# Base.net
KiCad netlist of a schematic drawn in EAGLE
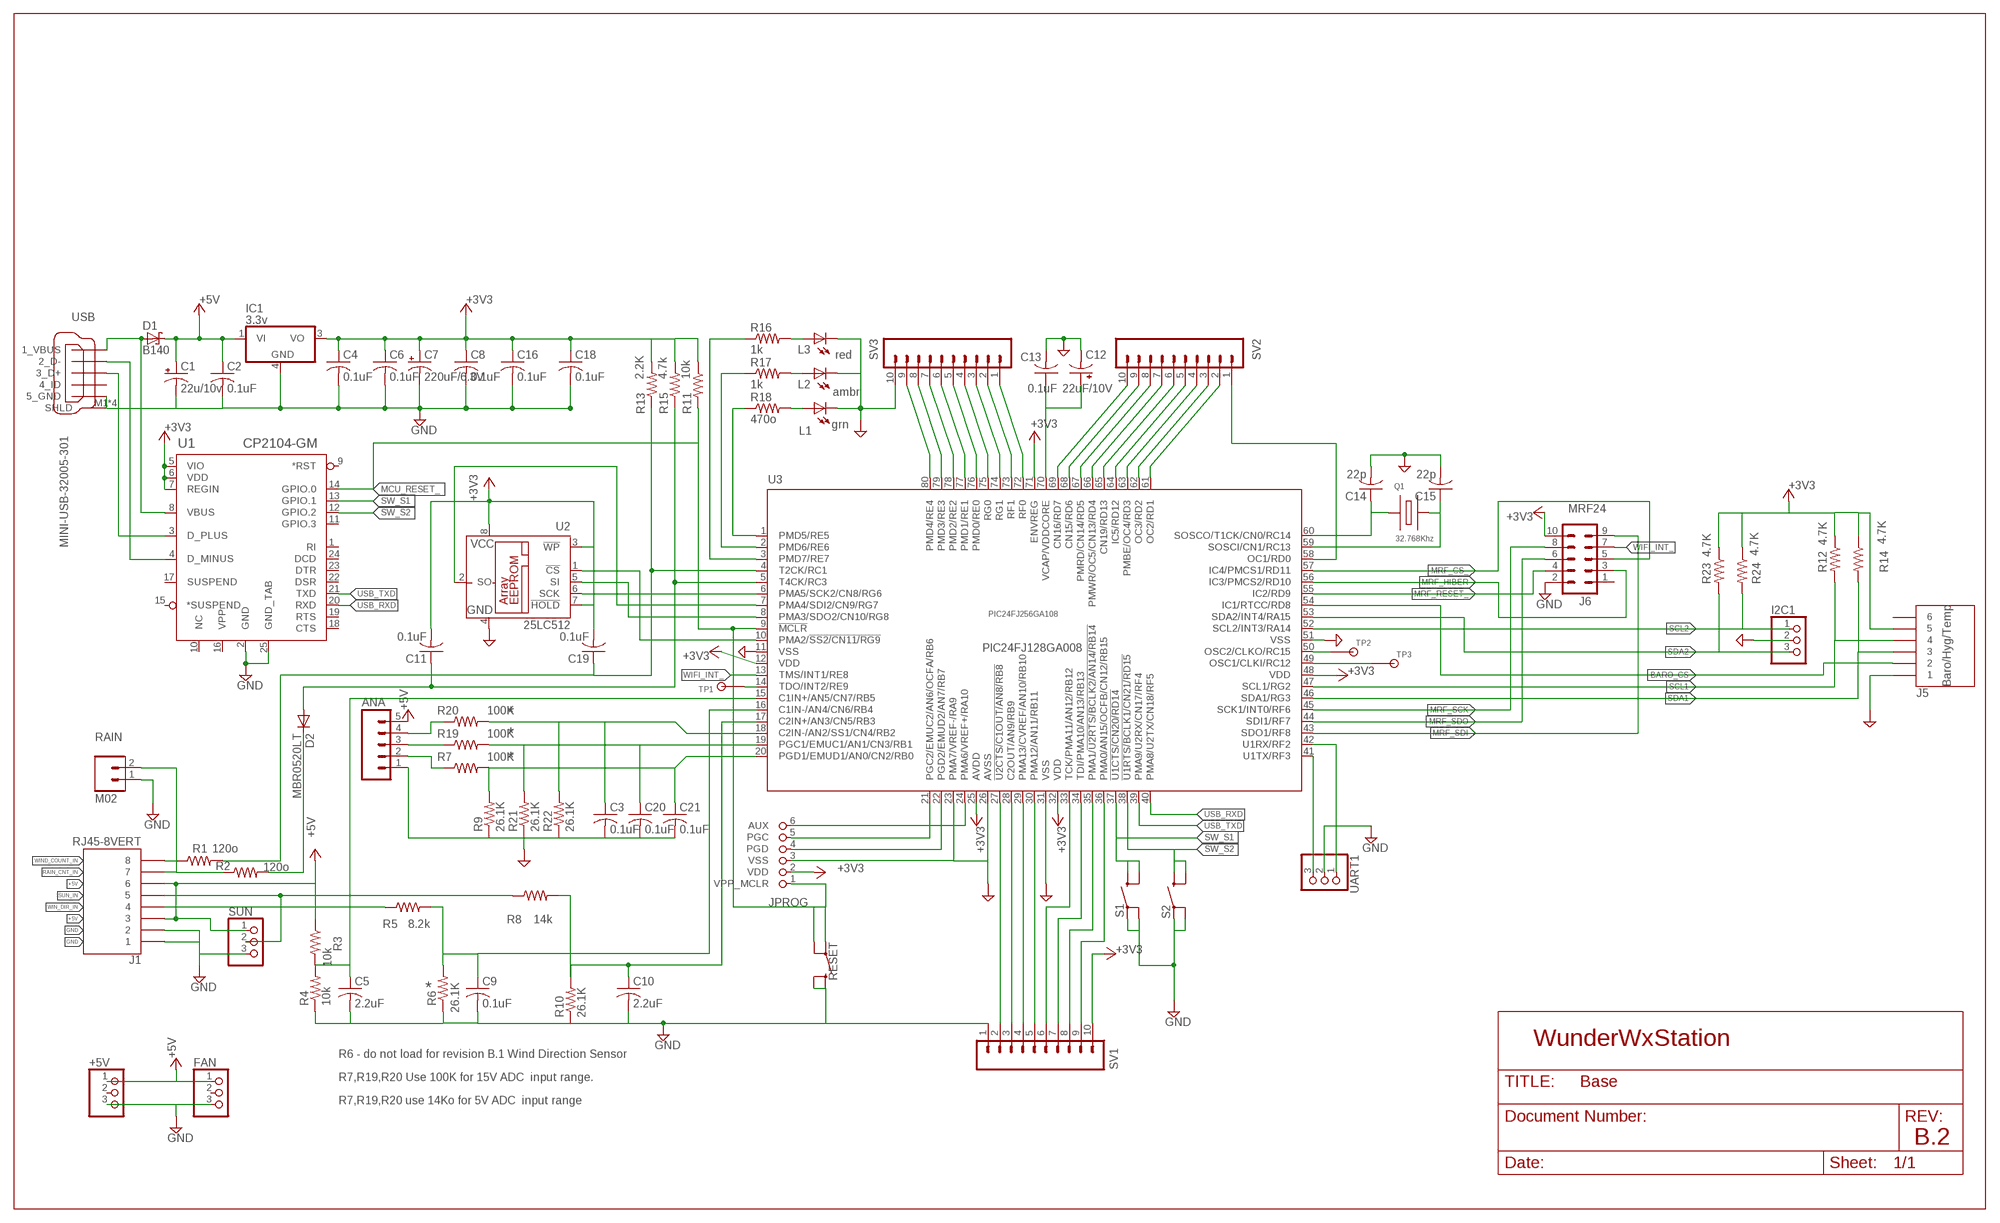
[diagram p0: schematic, sheet 1]

(export (version "E")
  (design (tool "Eeschema 10.0.6"))
  (components
    (comp (ref "+5V")
      (value "PINHD-1X3MOLEX_KK")
      (footprint "eagle-import:1X3_MOLEX_KK")
      (libsource (lib "eagle-import") (part "PINHD-1X3MOLEX_KK"))
    )
    (comp (ref "ANA")
      (value "M05PTH")
      (footprint "eagle-import:1X05")
      (libsource (lib "eagle-import") (part "M05PTH"))
    )
    (comp (ref "C1")
      (value "22u/10v")
      (footprint "eagle-import:SMC_B")
      (libsource (lib "eagle-import") (part "CPOL-USSMCB"))
    )
    (comp (ref "C2")
      (value "0.1uF")
      (footprint "eagle-import:C0805")
      (libsource (lib "eagle-import") (part "C-USC0805"))
    )
    (comp (ref "C3")
      (value "0.1uF")
      (footprint "eagle-import:C0805")
      (libsource (lib "eagle-import") (part "C-USC0805"))
    )
    (comp (ref "C4")
      (value "0.1uF")
      (footprint "eagle-import:C0805")
      (libsource (lib "eagle-import") (part "C-USC0805"))
    )
    (comp (ref "C5")
      (value "2.2uF")
      (footprint "eagle-import:C0805")
      (libsource (lib "eagle-import") (part "C-USC0805"))
    )
    (comp (ref "C6")
      (value "0.1uF")
      (footprint "eagle-import:C0805")
      (libsource (lib "eagle-import") (part "C-USC0805"))
    )
    (comp (ref "C7")
      (value "220uF/6.3V")
      (footprint "eagle-import:SMC_D")
      (libsource (lib "eagle-import") (part "CPOL-USSMCD"))
    )
    (comp (ref "C8")
      (value "0.1uF")
      (footprint "eagle-import:C0805")
      (libsource (lib "eagle-import") (part "C-USC0805"))
    )
    (comp (ref "C9")
      (value "0.1uF")
      (footprint "eagle-import:C0805")
      (libsource (lib "eagle-import") (part "C-USC0805"))
    )
    (comp (ref "C10")
      (value "2.2uF")
      (footprint "eagle-import:C0805")
      (libsource (lib "eagle-import") (part "C-USC0805"))
    )
    (comp (ref "C11")
      (value "0.1uF")
      (footprint "eagle-import:C0805")
      (libsource (lib "eagle-import") (part "C-USC0805"))
    )
    (comp (ref "C12")
      (value "22uF/10V")
      (footprint "eagle-import:SMC_B")
      (libsource (lib "eagle-import") (part "CPOL-USSMCB"))
    )
    (comp (ref "C13")
      (value "0.1uF")
      (footprint "eagle-import:C0805")
      (libsource (lib "eagle-import") (part "C-USC0805"))
    )
    (comp (ref "C14")
      (value "22p")
      (footprint "eagle-import:C0603")
      (libsource (lib "eagle-import") (part "C-USC0603"))
    )
    (comp (ref "C15")
      (value "22p")
      (footprint "eagle-import:C0603")
      (libsource (lib "eagle-import") (part "C-USC0603"))
    )
    (comp (ref "C16")
      (value "0.1uF")
      (footprint "eagle-import:C0805")
      (libsource (lib "eagle-import") (part "C-USC0805"))
    )
    (comp (ref "C18")
      (value "0.1uF")
      (footprint "eagle-import:C0805")
      (libsource (lib "eagle-import") (part "C-USC0805"))
    )
    (comp (ref "C19")
      (value "0.1uF")
      (footprint "eagle-import:C0805")
      (libsource (lib "eagle-import") (part "C-USC0805"))
    )
    (comp (ref "C20")
      (value "0.1uF")
      (footprint "eagle-import:C0805")
      (libsource (lib "eagle-import") (part "C-USC0805"))
    )
    (comp (ref "C21")
      (value "0.1uF")
      (footprint "eagle-import:C0805")
      (libsource (lib "eagle-import") (part "C-USC0805"))
    )
    (comp (ref "D1")
      (value "B140")
      (footprint "eagle-import:SMB")
      (libsource (lib "eagle-import") (part "SCHOTTKY-DIODESMD"))
    )
    (comp (ref "D2")
      (value "MBR0520LT")
      (footprint "eagle-import:SOD123")
      (libsource (lib "eagle-import") (part "MBR0520LT"))
    )
    (comp (ref "FAN")
      (value "PINHD-1X3MOLEX_KK")
      (footprint "eagle-import:1X3_MOLEX_KK")
      (libsource (lib "eagle-import") (part "PINHD-1X3MOLEX_KK"))
    )
    (comp (ref "I2C1")
      (value "PINHD-1X3")
      (footprint "eagle-import:1X03")
      (libsource (lib "eagle-import") (part "PINHD-1X3"))
    )
    (comp (ref "IC1")
      (value "3.3v")
      (footprint "eagle-import:DPACK")
      (libsource (lib "eagle-import") (part "78MXXL"))
    )
    (comp (ref "J1")
      (value "RJ45-8VERT")
      (footprint "eagle-import:RJ45_VERT")
      (libsource (lib "eagle-import") (part "RJ45-8VERT"))
    )
    (comp (ref "J5")
      (value "RJ11-6VERT_LP")
      (footprint "eagle-import:RJ11-6-VERT")
      (libsource (lib "eagle-import") (part "RJ11-6VERT_LP"))
    )
    (comp (ref "J6")
      (value "M05X22X5FE")
      (footprint "eagle-import:2X5FEMALE")
      (libsource (lib "eagle-import") (part "M05X22X5FE"))
    )
    (comp (ref "JPROG")
      (value "PIKIT2_PRG")
      (footprint "eagle-import:1X06_PIKIT")
      (libsource (lib "eagle-import") (part "PIKIT2_PRG"))
    )
    (comp (ref "L1")
      (value "grn")
      (footprint "eagle-import:CHIP-LED0603")
      (libsource (lib "eagle-import") (part "LEDCHIP-LED0603"))
    )
    (comp (ref "L2")
      (value "ambr")
      (footprint "eagle-import:CHIP-LED0603")
      (libsource (lib "eagle-import") (part "LEDCHIP-LED0603"))
    )
    (comp (ref "L3")
      (value "red")
      (footprint "eagle-import:CHIP-LED0603")
      (libsource (lib "eagle-import") (part "LEDCHIP-LED0603"))
    )
    (comp (ref "Q1")
      (value "32.768Khz")
      (footprint "eagle-import:CRYSTAL32_SMT")
      (libsource (lib "eagle-import") (part "CRYSTAL"))
    )
    (comp (ref "R1")
      (value "120o")
      (footprint "eagle-import:R0603")
      (libsource (lib "eagle-import") (part "R-US_R0603"))
    )
    (comp (ref "R2")
      (value "120o")
      (footprint "eagle-import:R0603")
      (libsource (lib "eagle-import") (part "R-US_R0603"))
    )
    (comp (ref "R3")
      (value "10k")
      (footprint "eagle-import:R0603")
      (libsource (lib "eagle-import") (part "R-US_R0603"))
    )
    (comp (ref "R4")
      (value "10k")
      (footprint "eagle-import:R0603")
      (libsource (lib "eagle-import") (part "R-US_R0603"))
    )
    (comp (ref "R5")
      (value "8.2k")
      (footprint "eagle-import:R0603")
      (libsource (lib "eagle-import") (part "R-US_R0603"))
    )
    (comp (ref "R6")
      (value "26.1K")
      (footprint "eagle-import:R0603")
      (libsource (lib "eagle-import") (part "R-US_R0603"))
    )
    (comp (ref "R7")
      (value "100K")
      (footprint "eagle-import:R0603")
      (libsource (lib "eagle-import") (part "R-US_R0603"))
    )
    (comp (ref "R8")
      (value "14k")
      (footprint "eagle-import:R0603")
      (libsource (lib "eagle-import") (part "R-US_R0603"))
    )
    (comp (ref "R9")
      (value "26.1K")
      (footprint "eagle-import:R0603")
      (libsource (lib "eagle-import") (part "R-US_R0603"))
    )
    (comp (ref "R10")
      (value "26.1K")
      (footprint "eagle-import:R0603")
      (libsource (lib "eagle-import") (part "R-US_R0603"))
    )
    (comp (ref "R11")
      (value "10k")
      (footprint "eagle-import:R0603")
      (libsource (lib "eagle-import") (part "R-US_R0603"))
    )
    (comp (ref "R12")
      (value "4.7K")
      (footprint "eagle-import:R0603")
      (libsource (lib "eagle-import") (part "R-US_R0603"))
    )
    (comp (ref "R13")
      (value "2.2K")
      (footprint "eagle-import:R0603")
      (libsource (lib "eagle-import") (part "R-US_R0603"))
    )
    (comp (ref "R14")
      (value "4.7K")
      (footprint "eagle-import:R0603")
      (libsource (lib "eagle-import") (part "R-US_R0603"))
    )
    (comp (ref "R15")
      (value "4.7k")
      (footprint "eagle-import:R0603")
      (libsource (lib "eagle-import") (part "R-US_R0603"))
    )
    (comp (ref "R16")
      (value "1k")
      (footprint "eagle-import:R0603")
      (libsource (lib "eagle-import") (part "R-US_R0603"))
    )
    (comp (ref "R17")
      (value "1k")
      (footprint "eagle-import:R0603")
      (libsource (lib "eagle-import") (part "R-US_R0603"))
    )
    (comp (ref "R18")
      (value "470o")
      (footprint "eagle-import:R0603")
      (libsource (lib "eagle-import") (part "R-US_R0603"))
    )
    (comp (ref "R19")
      (value "100K")
      (footprint "eagle-import:R0603")
      (libsource (lib "eagle-import") (part "R-US_R0603"))
    )
    (comp (ref "R20")
      (value "100K")
      (footprint "eagle-import:R0603")
      (libsource (lib "eagle-import") (part "R-US_R0603"))
    )
    (comp (ref "R21")
      (value "26.1K")
      (footprint "eagle-import:R0603")
      (libsource (lib "eagle-import") (part "R-US_R0603"))
    )
    (comp (ref "R22")
      (value "26.1K")
      (footprint "eagle-import:R0603")
      (libsource (lib "eagle-import") (part "R-US_R0603"))
    )
    (comp (ref "R23")
      (value "4.7K")
      (footprint "eagle-import:R0603")
      (libsource (lib "eagle-import") (part "R-US_R0603"))
    )
    (comp (ref "R24")
      (value "4.7K")
      (footprint "eagle-import:R0603")
      (libsource (lib "eagle-import") (part "R-US_R0603"))
    )
    (comp (ref "RAIN")
      (value "M02")
      (footprint "eagle-import:1X02")
      (libsource (lib "eagle-import") (part "M02"))
    )
    (comp (ref "RESET")
      (value "SWITCH-MOMENTARY-2SMD")
      (footprint "eagle-import:TACTILE_SWITCH_SMD")
      (libsource (lib "eagle-import") (part "SWITCH-MOMENTARY-2SMD"))
    )
    (comp (ref "S1")
      (value "SWITCH-MOMENTARY-2SMD")
      (footprint "eagle-import:TACTILE_SWITCH_SMD")
      (libsource (lib "eagle-import") (part "SWITCH-MOMENTARY-2SMD"))
    )
    (comp (ref "S2")
      (value "SWITCH-MOMENTARY-2SMD")
      (footprint "eagle-import:TACTILE_SWITCH_SMD")
      (libsource (lib "eagle-import") (part "SWITCH-MOMENTARY-2SMD"))
    )
    (comp (ref "SUN")
      (value "PINHD-1X3MOLEX_KK")
      (footprint "eagle-import:1X3_MOLEX_KK")
      (libsource (lib "eagle-import") (part "PINHD-1X3MOLEX_KK"))
    )
    (comp (ref "SV1")
      (value "M10\"")
      (footprint "eagle-import:1X10")
      (libsource (lib "eagle-import") (part "M10{dblquote}"))
    )
    (comp (ref "SV2")
      (value "M10\"")
      (footprint "eagle-import:1X10")
      (libsource (lib "eagle-import") (part "M10{dblquote}"))
    )
    (comp (ref "SV3")
      (value "M10\"")
      (footprint "eagle-import:1X10")
      (libsource (lib "eagle-import") (part "M10{dblquote}"))
    )
    (comp (ref "TP1")
      (value "TP10R")
      (footprint "eagle-import:TP10R")
      (libsource (lib "eagle-import") (part "TP10R"))
    )
    (comp (ref "TP2")
      (value "TP6R")
      (footprint "eagle-import:TP06R")
      (libsource (lib "eagle-import") (part "TP6R"))
    )
    (comp (ref "TP3")
      (value "TP6R")
      (footprint "eagle-import:TP06R")
      (libsource (lib "eagle-import") (part "TP6R"))
    )
    (comp (ref "U1")
      (value "CP2104-GM")
      (footprint "eagle-import:QFN24_4X4")
      (libsource (lib "eagle-import") (part "CP2104-GM"))
    )
    (comp (ref "U2")
      (value "25LC512")
      (footprint "eagle-import:SO-08")
      (fields (field (name "MF") "MICROCHIP") (field (name "MPN") "25LC080/SN"))
      (libsource (lib "eagle-import") (part "25SNLC080"))
    )
    (comp (ref "U3")
      (value "PIC24FJ128GA008")
      (footprint "eagle-import:TQFP80-12X12")
      (fields (field (name "MF") "MICROCHIP") (field (name "MPN") "PIC24FJ128GA008-I/PT"))
      (libsource (lib "eagle-import") (part "PIC24FJGA008128"))
    )
    (comp (ref "UART1")
      (value "PINHD-1X3")
      (footprint "eagle-import:1X03")
      (libsource (lib "eagle-import") (part "PINHD-1X3"))
    )
    (comp (ref "USB")
      (value "MINI-USB-32005-301")
      (footprint "eagle-import:32005-301")
      (libsource (lib "eagle-import") (part "MINI-USB-32005-301"))
    )
  )
  (nets
    (net (code "1") (name "+3V3") (class "Default")
      (node (ref "C11") (pin "2") (pinfunction "2_2") (pintype "passive"))
      (node (ref "C16") (pin "1") (pinfunction "1_1") (pintype "passive"))
      (node (ref "C18") (pin "1") (pinfunction "1_1") (pintype "passive"))
      (node (ref "C19") (pin "2") (pinfunction "2_2") (pintype "passive"))
      (node (ref "C4") (pin "1") (pinfunction "1_1") (pintype "passive"))
      (node (ref "C6") (pin "1") (pinfunction "1_1") (pintype "passive"))
      (node (ref "C7") (pin "+") (pinfunction "+_+") (pintype "passive"))
      (node (ref "C8") (pin "1") (pinfunction "1_1") (pintype "passive"))
      (node (ref "IC1") (pin "3") (pinfunction "VO_3") (pintype "passive"))
      (node (ref "J5") (pin "P$5") (pinfunction "5_P$5") (pintype "bidirectional"))
      (node (ref "J6") (pin "10") (pinfunction "10_10") (pintype "passive"))
      (node (ref "JPROG") (pin "2") (pinfunction "VDD_2") (pintype "passive"))
      (node (ref "R11") (pin "1") (pinfunction "1_1") (pintype "passive"))
      (node (ref "R12") (pin "1") (pinfunction "1_1") (pintype "passive"))
      (node (ref "R13") (pin "2") (pinfunction "2_2") (pintype "passive"))
      (node (ref "R14") (pin "1") (pinfunction "1_1") (pintype "passive"))
      (node (ref "R15") (pin "2") (pinfunction "2_2") (pintype "passive"))
      (node (ref "R23") (pin "1") (pinfunction "1_1") (pintype "passive"))
      (node (ref "R24") (pin "1") (pinfunction "1_1") (pintype "passive"))
      (node (ref "SV1") (pin "10") (pinfunction "10_10") (pintype "passive"))
      (node (ref "U1") (pin "5") (pinfunction "VIO_5") (pintype "power_in"))
      (node (ref "U1") (pin "6") (pinfunction "VDD_6") (pintype "power_in"))
      (node (ref "U1") (pin "7") (pinfunction "REGIN_7") (pintype "input"))
      (node (ref "U2") (pin "3") (pinfunction "~{WP}_3") (pintype "input"))
      (node (ref "U2") (pin "7") (pinfunction "~{HOLD}_7") (pintype "input"))
      (node (ref "U2") (pin "8") (pinfunction "VCC_8") (pintype "power_in"))
      (node (ref "U3") (pin "12") (pinfunction "VDD_12") (pintype "power_in"))
      (node (ref "U3") (pin "25") (pinfunction "AVDD_25") (pintype "power_in"))
      (node (ref "U3") (pin "32") (pinfunction "VDD_32") (pintype "power_in"))
      (node (ref "U3") (pin "48") (pinfunction "VDD_48") (pintype "power_in"))
      (node (ref "U3") (pin "71") (pinfunction "ENVREG_71") (pintype "bidirectional"))
    )
    (net (code "2") (name "+5V") (class "Default")
      (node (ref "+5V") (pin "1") (pinfunction "1_1") (pintype "passive"))
      (node (ref "ANA") (pin "5") (pinfunction "5_5") (pintype "passive"))
      (node (ref "C1") (pin "+") (pinfunction "+_+") (pintype "passive"))
      (node (ref "C2") (pin "1") (pinfunction "1_1") (pintype "passive"))
      (node (ref "D1") (pin "C") (pinfunction "C_C") (pintype "passive"))
      (node (ref "FAN") (pin "1") (pinfunction "1_1") (pintype "passive"))
      (node (ref "IC1") (pin "1") (pinfunction "VI_1") (pintype "input"))
      (node (ref "J1") (pin "P$3") (pinfunction "3_P$3") (pintype "bidirectional"))
      (node (ref "J1") (pin "P$6") (pinfunction "6_P$6") (pintype "bidirectional"))
      (node (ref "R3") (pin "1") (pinfunction "1_1") (pintype "passive"))
      (node (ref "SUN") (pin "1") (pinfunction "1_1") (pintype "passive"))
    )
    (net (code "3") (name "BARO_CS") (class "Default")
      (node (ref "J5") (pin "P$2") (pinfunction "2_P$2") (pintype "bidirectional"))
      (node (ref "U3") (pin "54") (pinfunction "IC1/RTCC/RD8_54") (pintype "bidirectional"))
    )
    (net (code "4") (name "GND") (class "Default")
      (node (ref "+5V") (pin "3") (pinfunction "3_3") (pintype "passive"))
      (node (ref "ANA") (pin "1") (pinfunction "1_1") (pintype "passive"))
      (node (ref "C1") (pin "-") (pinfunction "-_-") (pintype "passive"))
      (node (ref "C10") (pin "2") (pinfunction "2_2") (pintype "passive"))
      (node (ref "C12") (pin "-") (pinfunction "-_-") (pintype "passive"))
      (node (ref "C13") (pin "2") (pinfunction "2_2") (pintype "passive"))
      (node (ref "C14") (pin "2") (pinfunction "2_2") (pintype "passive"))
      (node (ref "C15") (pin "2") (pinfunction "2_2") (pintype "passive"))
      (node (ref "C16") (pin "2") (pinfunction "2_2") (pintype "passive"))
      (node (ref "C18") (pin "2") (pinfunction "2_2") (pintype "passive"))
      (node (ref "C2") (pin "2") (pinfunction "2_2") (pintype "passive"))
      (node (ref "C20") (pin "2") (pinfunction "2_2") (pintype "passive"))
      (node (ref "C21") (pin "2") (pinfunction "2_2") (pintype "passive"))
      (node (ref "C3") (pin "2") (pinfunction "2_2") (pintype "passive"))
      (node (ref "C4") (pin "2") (pinfunction "2_2") (pintype "passive"))
      (node (ref "C5") (pin "2") (pinfunction "2_2") (pintype "passive"))
      (node (ref "C6") (pin "2") (pinfunction "2_2") (pintype "passive"))
      (node (ref "C7") (pin "-") (pinfunction "-_-") (pintype "passive"))
      (node (ref "C8") (pin "2") (pinfunction "2_2") (pintype "passive"))
      (node (ref "C9") (pin "2") (pinfunction "2_2") (pintype "passive"))
      (node (ref "FAN") (pin "3") (pinfunction "3_3") (pintype "passive"))
      (node (ref "I2C1") (pin "2") (pinfunction "2_2") (pintype "passive"))
      (node (ref "IC1") (pin "4") (pinfunction "GND_4") (pintype "passive"))
      (node (ref "J1") (pin "P$1") (pinfunction "1_P$1") (pintype "bidirectional"))
      (node (ref "J1") (pin "P$2") (pinfunction "2_P$2") (pintype "bidirectional"))
      (node (ref "J5") (pin "P$1") (pinfunction "1_P$1") (pintype "bidirectional"))
      (node (ref "J6") (pin "2") (pinfunction "2_2") (pintype "passive"))
      (node (ref "JPROG") (pin "3") (pinfunction "VSS_3") (pintype "passive"))
      (node (ref "L1") (pin "C") (pinfunction "C_C") (pintype "passive"))
      (node (ref "L2") (pin "C") (pinfunction "C_C") (pintype "passive"))
      (node (ref "L3") (pin "C") (pinfunction "C_C") (pintype "passive"))
      (node (ref "R10") (pin "1") (pinfunction "1_1") (pintype "passive"))
      (node (ref "R21") (pin "1") (pinfunction "1_1") (pintype "passive"))
      (node (ref "R22") (pin "1") (pinfunction "1_1") (pintype "passive"))
      (node (ref "R4") (pin "1") (pinfunction "1_1") (pintype "passive"))
      (node (ref "R6") (pin "1") (pinfunction "1_1") (pintype "passive"))
      (node (ref "R9") (pin "1") (pinfunction "1_1") (pintype "passive"))
      (node (ref "RAIN") (pin "1") (pinfunction "1_1") (pintype "passive"))
      (node (ref "RESET") (pin "3") (pinfunction "2_3") (pintype "passive"))
      (node (ref "RESET") (pin "4") (pinfunction "3_4") (pintype "passive"))
      (node (ref "S1") (pin "1") (pinfunction "1_1") (pintype "passive"))
      (node (ref "S1") (pin "2") (pinfunction "4_2") (pintype "passive"))
      (node (ref "S2") (pin "1") (pinfunction "1_1") (pintype "passive"))
      (node (ref "S2") (pin "2") (pinfunction "4_2") (pintype "passive"))
      (node (ref "SUN") (pin "3") (pinfunction "3_3") (pintype "passive"))
      (node (ref "SV1") (pin "1") (pinfunction "1_1") (pintype "passive"))
      (node (ref "SV3") (pin "10") (pinfunction "10_10") (pintype "passive"))
      (node (ref "U1") (pin "2") (pinfunction "GND_2") (pintype "power_in"))
      (node (ref "U1") (pin "25") (pinfunction "GND_TAB_25") (pintype "passive"))
      (node (ref "U2") (pin "4") (pinfunction "GND_4") (pintype "power_in"))
      (node (ref "U3") (pin "11") (pinfunction "VSS_11") (pintype "power_in"))
      (node (ref "U3") (pin "23") (pinfunction "PMA7/VREF-/RA9_23") (pintype "bidirectional"))
      (node (ref "U3") (pin "26") (pinfunction "AVSS_26") (pintype "power_in"))
      (node (ref "U3") (pin "31") (pinfunction "VSS_31") (pintype "power_in"))
      (node (ref "U3") (pin "51") (pinfunction "VSS_51") (pintype "power_in"))
      (node (ref "UART1") (pin "2") (pinfunction "2_2") (pintype "passive"))
      (node (ref "USB") (pin "5_USB_GND") (pinfunction "5_GND_5_USB_GND") (pintype "passive"))
      (node (ref "USB") (pin "M1") (pinfunction "SHLD_M1") (pintype "passive"))
      (node (ref "USB") (pin "M2") (pinfunction "SHLD_M2") (pintype "passive"))
      (node (ref "USB") (pin "M3") (pinfunction "SHLD_M3") (pintype "passive"))
      (node (ref "USB") (pin "M4") (pinfunction "SHLD_M4") (pintype "passive"))
    )
    (net (code "5") (name "MCU_RESET_") (class "Default")
      (node (ref "JPROG") (pin "1") (pinfunction "VPP_MCLR_1") (pintype "passive"))
      (node (ref "R11") (pin "2") (pinfunction "2_2") (pintype "passive"))
      (node (ref "RESET") (pin "1") (pinfunction "1_1") (pintype "passive"))
      (node (ref "RESET") (pin "2") (pinfunction "4_2") (pintype "passive"))
      (node (ref "U1") (pin "14") (pinfunction "GPIO.0_14") (pintype "passive"))
      (node (ref "U3") (pin "9") (pinfunction "~{MCLR}_9") (pintype "bidirectional"))
    )
    (net (code "6") (name "MRF_CS_") (class "Default")
      (node (ref "J6") (pin "5") (pinfunction "5_5") (pintype "passive"))
      (node (ref "U3") (pin "57") (pinfunction "IC4/PMCS1/RD11_57") (pintype "bidirectional"))
    )
    (net (code "7") (name "MRF_HIBER") (class "Default")
      (node (ref "J6") (pin "3") (pinfunction "3_3") (pintype "passive"))
      (node (ref "U3") (pin "56") (pinfunction "IC3/PMCS2/RD10_56") (pintype "bidirectional"))
    )
    (net (code "8") (name "MRF_RESET_") (class "Default")
      (node (ref "J6") (pin "4") (pinfunction "4_4") (pintype "passive"))
      (node (ref "U3") (pin "55") (pinfunction "IC2/RD9_55") (pintype "bidirectional"))
    )
    (net (code "9") (name "MRF_SCK") (class "Default")
      (node (ref "J6") (pin "8") (pinfunction "8_8") (pintype "passive"))
      (node (ref "U3") (pin "45") (pinfunction "SCK1/INT0/RF6_45") (pintype "bidirectional"))
    )
    (net (code "10") (name "MRF_SDI") (class "Default")
      (node (ref "J6") (pin "9") (pinfunction "9_9") (pintype "passive"))
      (node (ref "U3") (pin "43") (pinfunction "SDO1/RF8_43") (pintype "bidirectional"))
    )
    (net (code "11") (name "MRF_SDO") (class "Default")
      (node (ref "J6") (pin "6") (pinfunction "6_6") (pintype "passive"))
      (node (ref "U3") (pin "44") (pinfunction "SDI1/RF7_44") (pintype "bidirectional"))
    )
    (net (code "12") (name "Net-(ANA-Pad2)") (class "Default")
      (node (ref "ANA") (pin "2") (pinfunction "2_2") (pintype "passive"))
      (node (ref "R7") (pin "1") (pinfunction "1_1") (pintype "passive"))
    )
    (net (code "13") (name "Net-(ANA-Pad3)") (class "Default")
      (node (ref "ANA") (pin "3") (pinfunction "3_3") (pintype "passive"))
      (node (ref "R19") (pin "1") (pinfunction "1_1") (pintype "passive"))
    )
    (net (code "14") (name "Net-(ANA-Pad4)") (class "Default")
      (node (ref "ANA") (pin "4") (pinfunction "4_4") (pintype "passive"))
      (node (ref "R20") (pin "1") (pinfunction "1_1") (pintype "passive"))
    )
    (net (code "15") (name "Net-(D2-PadC)") (class "Default")
      (node (ref "D2") (pin "C") (pinfunction "C_C") (pintype "passive"))
      (node (ref "R2") (pin "2") (pinfunction "2_2") (pintype "passive"))
    )
    (net (code "16") (name "Net-(JPROG-AUX)") (class "Default")
      (node (ref "JPROG") (pin "6") (pinfunction "AUX_6") (pintype "passive"))
      (node (ref "U3") (pin "24") (pinfunction "PMA6/VREF+/RA10_24") (pintype "bidirectional"))
    )
    (net (code "17") (name "Net-(JPROG-PGC)") (class "Default")
      (node (ref "JPROG") (pin "5") (pinfunction "PGC_5") (pintype "passive"))
      (node (ref "U3") (pin "21") (pinfunction "PGC2/EMUC2/AN6/OCFA/RB6_21") (pintype "bidirectional"))
    )
    (net (code "18") (name "Net-(JPROG-PGD)") (class "Default")
      (node (ref "JPROG") (pin "4") (pinfunction "PGD_4") (pintype "passive"))
      (node (ref "U3") (pin "22") (pinfunction "PGD2/EMUD2/AN7/RB7_22") (pintype "bidirectional"))
    )
    (net (code "19") (name "Net-(L1-PadA)") (class "Default")
      (node (ref "L1") (pin "A") (pinfunction "A_A") (pintype "passive"))
      (node (ref "R18") (pin "2") (pinfunction "2_2") (pintype "passive"))
    )
    (net (code "20") (name "Net-(L2-PadA)") (class "Default")
      (node (ref "L2") (pin "A") (pinfunction "A_A") (pintype "passive"))
      (node (ref "R17") (pin "2") (pinfunction "2_2") (pintype "passive"))
    )
    (net (code "21") (name "Net-(L3-PadA)") (class "Default")
      (node (ref "L3") (pin "A") (pinfunction "A_A") (pintype "passive"))
      (node (ref "R16") (pin "2") (pinfunction "2_2") (pintype "passive"))
    )
    (net (code "22") (name "Net-(Q1-P$1)") (class "Default")
      (node (ref "C14") (pin "1") (pinfunction "1_1") (pintype "passive"))
      (node (ref "Q1") (pin "P$2") (pinfunction "P$1_P$2") (pintype "bidirectional"))
      (node (ref "U3") (pin "60") (pinfunction "SOSCO/T1CK/CN0/RC14_60") (pintype "bidirectional"))
    )
    (net (code "23") (name "Net-(Q1-P$2)") (class "Default")
      (node (ref "C15") (pin "1") (pinfunction "1_1") (pintype "passive"))
      (node (ref "Q1") (pin "P$3") (pinfunction "P$2_P$3") (pintype "bidirectional"))
      (node (ref "U3") (pin "59") (pinfunction "SOSCI/CN1/RC13_59") (pintype "bidirectional"))
    )
    (net (code "24") (name "Net-(TP1-P$1)") (class "Default")
      (node (ref "TP1") (pin "TP_1") (pinfunction "P$1_TP_1") (pintype "bidirectional"))
      (node (ref "U3") (pin "14") (pinfunction "TDO/INT2/RE9_14") (pintype "bidirectional"))
    )
    (net (code "25") (name "Net-(TP2-P$1)") (class "Default")
      (node (ref "TP2") (pin "TP_1") (pinfunction "P$1_TP_1") (pintype "bidirectional"))
      (node (ref "U3") (pin "50") (pinfunction "OSC2/CLKO/RC15_50") (pintype "bidirectional"))
    )
    (net (code "26") (name "Net-(TP3-P$1)") (class "Default")
      (node (ref "TP3") (pin "TP_1") (pinfunction "P$1_TP_1") (pintype "bidirectional"))
      (node (ref "U3") (pin "49") (pinfunction "OSC1/CLKI/RC12_49") (pintype "bidirectional"))
    )
    (net (code "27") (name "Net-(U1-D_MINUS)") (class "Default")
      (node (ref "U1") (pin "4") (pinfunction "D_MINUS_4") (pintype "passive"))
      (node (ref "USB") (pin "2_D-") (pinfunction "2_D-_2_D-") (pintype "passive"))
    )
    (net (code "28") (name "Net-(U1-D_PLUS)") (class "Default")
      (node (ref "U1") (pin "3") (pinfunction "D_PLUS_3") (pintype "passive"))
      (node (ref "USB") (pin "3_D+") (pinfunction "3_D+_3_D+") (pintype "passive"))
    )
    (net (code "29") (name "Net-(U1-VBUS)") (class "Default")
      (node (ref "D1") (pin "A") (pinfunction "A_A") (pintype "passive"))
      (node (ref "U1") (pin "8") (pinfunction "VBUS_8") (pintype "input"))
      (node (ref "USB") (pin "1_VBUS") (pinfunction "1_VBUS_1_VBUS") (pintype "passive"))
    )
    (net (code "30") (name "Net-(U2-SCK)") (class "Default")
      (node (ref "U2") (pin "6") (pinfunction "SCK_6") (pintype "input"))
      (node (ref "U3") (pin "6") (pinfunction "PMA5/SCK2/CN8/RG6_6") (pintype "bidirectional"))
    )
    (net (code "31") (name "Net-(U2-SI)") (class "Default")
      (node (ref "U2") (pin "5") (pinfunction "SI_5") (pintype "input"))
      (node (ref "U3") (pin "8") (pinfunction "PMA3/SDO2/CN10/RG8_8") (pintype "bidirectional"))
    )
    (net (code "32") (name "Net-(U2-SO)") (class "Default")
      (node (ref "U2") (pin "2") (pinfunction "SO_2") (pintype "bidirectional"))
      (node (ref "U3") (pin "7") (pinfunction "PMA4/SDI2/CN9/RG7_7") (pintype "bidirectional"))
    )
    (net (code "33") (name "Net-(U2-~{CS})") (class "Default")
      (node (ref "U2") (pin "1") (pinfunction "~{CS}_1") (pintype "input"))
      (node (ref "U3") (pin "10") (pinfunction "PMA2/~{SS2/CN11/RG9}_10") (pintype "bidirectional"))
    )
    (net (code "34") (name "Net-(U3-C1IN+{slash}AN5{slash}CN7{slash}RB5)") (class "Default")
      (node (ref "C5") (pin "1") (pinfunction "1_1") (pintype "passive"))
      (node (ref "R3") (pin "2") (pinfunction "2_2") (pintype "passive"))
      (node (ref "R4") (pin "2") (pinfunction "2_2") (pintype "passive"))
      (node (ref "U3") (pin "15") (pinfunction "C1IN+/AN5/CN7/RB5_15") (pintype "bidirectional"))
    )
    (net (code "35") (name "Net-(U3-C1IN-{slash}AN4{slash}CN6{slash}RB4)") (class "Default")
      (node (ref "C9") (pin "1") (pinfunction "1_1") (pintype "passive"))
      (node (ref "R5") (pin "2") (pinfunction "2_2") (pintype "passive"))
      (node (ref "R6") (pin "2") (pinfunction "2_2") (pintype "passive"))
      (node (ref "U3") (pin "16") (pinfunction "C1IN-/AN4/CN6/RB4_16") (pintype "bidirectional"))
    )
    (net (code "36") (name "Net-(U3-C2IN+{slash}AN3{slash}CN5{slash}RB3)") (class "Default")
      (node (ref "C10") (pin "1") (pinfunction "1_1") (pintype "passive"))
      (node (ref "R10") (pin "2") (pinfunction "2_2") (pintype "passive"))
      (node (ref "R8") (pin "2") (pinfunction "2_2") (pintype "passive"))
      (node (ref "U3") (pin "17") (pinfunction "C2IN+/AN3/CN5/RB3_17") (pintype "bidirectional"))
    )
    (net (code "37") (name "Net-(U3-C2IN-{slash}AN2{slash}SS1{slash}CN4{slash}RB2)") (class "Default")
      (node (ref "C3") (pin "1") (pinfunction "1_1") (pintype "passive"))
      (node (ref "R20") (pin "2") (pinfunction "2_2") (pintype "passive"))
      (node (ref "R22") (pin "2") (pinfunction "2_2") (pintype "passive"))
      (node (ref "U3") (pin "18") (pinfunction "C2IN-/AN2/SS1/CN4/RB2_18") (pintype "bidirectional"))
    )
    (net (code "38") (name "Net-(U3-C2OUT{slash}AN9{slash}RB9)") (class "Default")
      (node (ref "SV1") (pin "3") (pinfunction "3_3") (pintype "passive"))
      (node (ref "U3") (pin "28") (pinfunction "C2OUT/AN9/RB9_28") (pintype "bidirectional"))
    )
    (net (code "39") (name "Net-(U3-CN15{slash}RD6)") (class "Default")
      (node (ref "SV2") (pin "9") (pinfunction "9_9") (pintype "passive"))
      (node (ref "U3") (pin "68") (pinfunction "CN15/RD6_68") (pintype "bidirectional"))
    )
    (net (code "40") (name "Net-(U3-CN16{slash}RD7)") (class "Default")
      (node (ref "SV2") (pin "10") (pinfunction "10_10") (pintype "passive"))
      (node (ref "U3") (pin "69") (pinfunction "CN16/RD7_69") (pintype "bidirectional"))
    )
    (net (code "41") (name "Net-(U3-CN19{slash}RD13)") (class "Default")
      (node (ref "SV2") (pin "6") (pinfunction "6_6") (pintype "passive"))
      (node (ref "U3") (pin "65") (pinfunction "CN19/RD13_65") (pintype "bidirectional"))
    )
    (net (code "42") (name "Net-(U3-IC5{slash}RD12)") (class "Default")
      (node (ref "SV2") (pin "5") (pinfunction "5_5") (pintype "passive"))
      (node (ref "U3") (pin "64") (pinfunction "IC5/RD12_64") (pintype "bidirectional"))
    )
    (net (code "43") (name "Net-(U3-OC1{slash}RD0)") (class "Default")
      (node (ref "SV2") (pin "1") (pinfunction "1_1") (pintype "passive"))
      (node (ref "U3") (pin "58") (pinfunction "OC1/RD0_58") (pintype "bidirectional"))
    )
    (net (code "44") (name "Net-(U3-OC2{slash}RD1)") (class "Default")
      (node (ref "SV2") (pin "2") (pinfunction "2_2") (pintype "passive"))
      (node (ref "U3") (pin "61") (pinfunction "OC2/RD1_61") (pintype "bidirectional"))
    )
    (net (code "45") (name "Net-(U3-OC3{slash}RD2)") (class "Default")
      (node (ref "SV2") (pin "3") (pinfunction "3_3") (pintype "passive"))
      (node (ref "U3") (pin "62") (pinfunction "OC3/RD2_62") (pintype "bidirectional"))
    )
    (net (code "46") (name "Net-(U3-PGC1{slash}EMUC1{slash}AN1{slash}CN3{slash}RB1)") (class "Default")
      (node (ref "C20") (pin "1") (pinfunction "1_1") (pintype "passive"))
      (node (ref "R19") (pin "2") (pinfunction "2_2") (pintype "passive"))
      (node (ref "R21") (pin "2") (pinfunction "2_2") (pintype "passive"))
      (node (ref "U3") (pin "19") (pinfunction "PGC1/EMUC1/AN1/CN3/RB1_19") (pintype "bidirectional"))
    )
    (net (code "47") (name "Net-(U3-PGD1{slash}EMUD1{slash}AN0{slash}CN2{slash}RB0)") (class "Default")
      (node (ref "C21") (pin "1") (pinfunction "1_1") (pintype "passive"))
      (node (ref "R7") (pin "2") (pinfunction "2_2") (pintype "passive"))
      (node (ref "R9") (pin "2") (pinfunction "2_2") (pintype "passive"))
      (node (ref "U3") (pin "20") (pinfunction "PGD1/EMUD1/AN0/CN2/RB0_20") (pintype "bidirectional"))
    )
    (net (code "48") (name "Net-(U3-PMA0{slash}AN15{slash}OCFB{slash}CN12{slash}RB15)") (class "Default")
      (node (ref "SV1") (pin "9") (pinfunction "9_9") (pintype "passive"))
      (node (ref "U3") (pin "36") (pinfunction "PMA0/AN15/OCFB/CN12/RB15_36") (pintype "bidirectional"))
    )
    (net (code "49") (name "Net-(U3-PMA1{slash}~{U2RTS{slash}BCLK2{slash}AN14{slash}RB14})") (class "Default")
      (node (ref "SV1") (pin "8") (pinfunction "8_8") (pintype "passive"))
      (node (ref "U3") (pin "35") (pinfunction "PMA1/~{U2RTS/BCLK2/AN14/RB14}_35") (pintype "bidirectional"))
    )
    (net (code "50") (name "Net-(U3-PMA12{slash}AN11{slash}RB11)") (class "Default")
      (node (ref "SV1") (pin "5") (pinfunction "5_5") (pintype "passive"))
      (node (ref "U3") (pin "30") (pinfunction "PMA12/AN11/RB11_30") (pintype "bidirectional"))
    )
    (net (code "51") (name "Net-(U3-PMA13{slash}CVREF{slash}AN10{slash}RB10)") (class "Default")
      (node (ref "SV1") (pin "4") (pinfunction "4_4") (pintype "passive"))
      (node (ref "U3") (pin "29") (pinfunction "PMA13/CVREF/AN10/RB10_29") (pintype "bidirectional"))
    )
    (net (code "52") (name "Net-(U3-PMBE{slash}OC4{slash}RD3)") (class "Default")
      (node (ref "SV2") (pin "4") (pinfunction "4_4") (pintype "passive"))
      (node (ref "U3") (pin "63") (pinfunction "PMBE/OC4/RD3_63") (pintype "bidirectional"))
    )
    (net (code "53") (name "Net-(U3-PMD0{slash}RE0)") (class "Default")
      (node (ref "SV3") (pin "5") (pinfunction "5_5") (pintype "passive"))
      (node (ref "U3") (pin "76") (pinfunction "PMD0/RE0_76") (pintype "bidirectional"))
    )
    (net (code "54") (name "Net-(U3-PMD1{slash}RE1)") (class "Default")
      (node (ref "SV3") (pin "6") (pinfunction "6_6") (pintype "passive"))
      (node (ref "U3") (pin "77") (pinfunction "PMD1/RE1_77") (pintype "bidirectional"))
    )
    (net (code "55") (name "Net-(U3-PMD2{slash}RE2)") (class "Default")
      (node (ref "SV3") (pin "7") (pinfunction "7_7") (pintype "passive"))
      (node (ref "U3") (pin "78") (pinfunction "PMD2/RE2_78") (pintype "bidirectional"))
    )
    (net (code "56") (name "Net-(U3-PMD3{slash}RE3)") (class "Default")
      (node (ref "SV3") (pin "8") (pinfunction "8_8") (pintype "passive"))
      (node (ref "U3") (pin "79") (pinfunction "PMD3/RE3_79") (pintype "bidirectional"))
    )
    (net (code "57") (name "Net-(U3-PMD4{slash}RE4)") (class "Default")
      (node (ref "SV3") (pin "9") (pinfunction "9_9") (pintype "passive"))
      (node (ref "U3") (pin "80") (pinfunction "PMD4/RE4_80") (pintype "bidirectional"))
    )
    (net (code "58") (name "Net-(U3-PMD5{slash}RE5)") (class "Default")
      (node (ref "R18") (pin "1") (pinfunction "1_1") (pintype "passive"))
      (node (ref "U3") (pin "1") (pinfunction "PMD5/RE5_1") (pintype "bidirectional"))
    )
    (net (code "59") (name "Net-(U3-PMD6{slash}RE6)") (class "Default")
      (node (ref "R17") (pin "1") (pinfunction "1_1") (pintype "passive"))
      (node (ref "U3") (pin "2") (pinfunction "PMD6/RE6_2") (pintype "bidirectional"))
    )
    (net (code "60") (name "Net-(U3-PMD7{slash}RE7)") (class "Default")
      (node (ref "R16") (pin "1") (pinfunction "1_1") (pintype "passive"))
      (node (ref "U3") (pin "3") (pinfunction "PMD7/RE7_3") (pintype "bidirectional"))
    )
    (net (code "61") (name "Net-(U3-PMRD{slash}CN14{slash}RD5)") (class "Default")
      (node (ref "SV2") (pin "8") (pinfunction "8_8") (pintype "passive"))
      (node (ref "U3") (pin "67") (pinfunction "PMRD/CN14/RD5_67") (pintype "bidirectional"))
    )
    (net (code "62") (name "Net-(U3-PMWR{slash}OC5{slash}CN13{slash}RD4)") (class "Default")
      (node (ref "SV2") (pin "7") (pinfunction "7_7") (pintype "passive"))
      (node (ref "U3") (pin "66") (pinfunction "PMWR/OC5/CN13/RD4_66") (pintype "bidirectional"))
    )
    (net (code "63") (name "Net-(U3-RF0)") (class "Default")
      (node (ref "SV3") (pin "1") (pinfunction "1_1") (pintype "passive"))
      (node (ref "U3") (pin "72") (pinfunction "RF0_72") (pintype "bidirectional"))
    )
    (net (code "64") (name "Net-(U3-RF1)") (class "Default")
      (node (ref "SV3") (pin "2") (pinfunction "2_2") (pintype "passive"))
      (node (ref "U3") (pin "73") (pinfunction "RF1_73") (pintype "bidirectional"))
    )
    (net (code "65") (name "Net-(U3-RG0)") (class "Default")
      (node (ref "SV3") (pin "4") (pinfunction "4_4") (pintype "passive"))
      (node (ref "U3") (pin "75") (pinfunction "RG0_75") (pintype "bidirectional"))
    )
    (net (code "66") (name "Net-(U3-RG1)") (class "Default")
      (node (ref "SV3") (pin "3") (pinfunction "3_3") (pintype "passive"))
      (node (ref "U3") (pin "74") (pinfunction "RG1_74") (pintype "bidirectional"))
    )
    (net (code "67") (name "Net-(U3-T2CK{slash}RC1)") (class "Default")
      (node (ref "C19") (pin "1") (pinfunction "1_1") (pintype "passive"))
      (node (ref "R1") (pin "2") (pinfunction "2_2") (pintype "passive"))
      (node (ref "R13") (pin "1") (pinfunction "1_1") (pintype "passive"))
      (node (ref "U3") (pin "4") (pinfunction "T2CK/RC1_4") (pintype "bidirectional"))
    )
    (net (code "68") (name "Net-(U3-T4CK{slash}RC3)") (class "Default")
      (node (ref "C11") (pin "1") (pinfunction "1_1") (pintype "passive"))
      (node (ref "D2") (pin "A") (pinfunction "A_A") (pintype "passive"))
      (node (ref "R15") (pin "1") (pinfunction "1_1") (pintype "passive"))
      (node (ref "U3") (pin "5") (pinfunction "T4CK/RC3_5") (pintype "bidirectional"))
    )
    (net (code "69") (name "Net-(U3-TCK{slash}PMA11{slash}AN12{slash}RB12)") (class "Default")
      (node (ref "SV1") (pin "6") (pinfunction "6_6") (pintype "passive"))
      (node (ref "U3") (pin "33") (pinfunction "TCK/PMA11/AN12/RB12_33") (pintype "bidirectional"))
    )
    (net (code "70") (name "Net-(U3-TDI{slash}PMA10{slash}AN13{slash}RB13)") (class "Default")
      (node (ref "SV1") (pin "7") (pinfunction "7_7") (pintype "passive"))
      (node (ref "U3") (pin "34") (pinfunction "TDI/PMA10/AN13/RB13_34") (pintype "bidirectional"))
    )
    (net (code "71") (name "Net-(U3-U1RX{slash}RF2)") (class "Default")
      (node (ref "U3") (pin "42") (pinfunction "U1RX/RF2_42") (pintype "bidirectional"))
      (node (ref "UART1") (pin "1") (pinfunction "1_1") (pintype "passive"))
    )
    (net (code "72") (name "Net-(U3-U1TX{slash}RF3)") (class "Default")
      (node (ref "U3") (pin "41") (pinfunction "U1TX/RF3_41") (pintype "bidirectional"))
      (node (ref "UART1") (pin "3") (pinfunction "3_3") (pintype "passive"))
    )
    (net (code "73") (name "Net-(U3-VCAP{slash}VDDCORE)") (class "Default")
      (node (ref "C12") (pin "+") (pinfunction "+_+") (pintype "passive"))
      (node (ref "C13") (pin "1") (pinfunction "1_1") (pintype "passive"))
      (node (ref "U3") (pin "70") (pinfunction "VCAP/VDDCORE_70") (pintype "bidirectional"))
    )
    (net (code "74") (name "Net-(U3-~{U2CTS{slash}C1OUT{slash}AN8{slash}RB8})") (class "Default")
      (node (ref "SV1") (pin "2") (pinfunction "2_2") (pintype "passive"))
      (node (ref "U3") (pin "27") (pinfunction "~{U2CTS/C1OUT/AN8/RB8}_27") (pintype "bidirectional"))
    )
    (net (code "75") (name "RAIN_CNT_IN") (class "Default")
      (node (ref "J1") (pin "P$7") (pinfunction "7_P$7") (pintype "bidirectional"))
      (node (ref "R2") (pin "1") (pinfunction "1_1") (pintype "passive"))
      (node (ref "RAIN") (pin "2") (pinfunction "2_2") (pintype "passive"))
    )
    (net (code "76") (name "SCL1") (class "Default")
      (node (ref "J5") (pin "P$4") (pinfunction "4_P$4") (pintype "bidirectional"))
      (node (ref "R12") (pin "2") (pinfunction "2_2") (pintype "passive"))
      (node (ref "U3") (pin "47") (pinfunction "SCL1/RG2_47") (pintype "bidirectional"))
    )
    (net (code "77") (name "SCL2") (class "Default")
      (node (ref "I2C1") (pin "1") (pinfunction "1_1") (pintype "passive"))
      (node (ref "R24") (pin "2") (pinfunction "2_2") (pintype "passive"))
      (node (ref "U3") (pin "52") (pinfunction "SCL2/INT3/RA14_52") (pintype "bidirectional"))
    )
    (net (code "78") (name "SDA1") (class "Default")
      (node (ref "J5") (pin "P$3") (pinfunction "3_P$3") (pintype "bidirectional"))
      (node (ref "R14") (pin "2") (pinfunction "2_2") (pintype "passive"))
      (node (ref "U3") (pin "46") (pinfunction "SDA1/RG3_46") (pintype "bidirectional"))
    )
    (net (code "79") (name "SDA2") (class "Default")
      (node (ref "I2C1") (pin "3") (pinfunction "3_3") (pintype "passive"))
      (node (ref "R23") (pin "2") (pinfunction "2_2") (pintype "passive"))
      (node (ref "U3") (pin "53") (pinfunction "SDA2/INT4/RA15_53") (pintype "bidirectional"))
    )
    (net (code "80") (name "SUN_IN") (class "Default")
      (node (ref "J1") (pin "P$5") (pinfunction "5_P$5") (pintype "bidirectional"))
      (node (ref "R8") (pin "1") (pinfunction "1_1") (pintype "passive"))
      (node (ref "SUN") (pin "2") (pinfunction "2_2") (pintype "passive"))
    )
    (net (code "81") (name "SW_S1") (class "Default")
      (node (ref "S1") (pin "3") (pinfunction "2_3") (pintype "passive"))
      (node (ref "S1") (pin "4") (pinfunction "3_4") (pintype "passive"))
      (node (ref "U1") (pin "13") (pinfunction "GPIO.1_13") (pintype "passive"))
      (node (ref "U3") (pin "37") (pinfunction "~{U1CTS/CN20/RD14}_37") (pintype "bidirectional"))
    )
    (net (code "82") (name "SW_S2") (class "Default")
      (node (ref "S2") (pin "3") (pinfunction "2_3") (pintype "passive"))
      (node (ref "S2") (pin "4") (pinfunction "3_4") (pintype "passive"))
      (node (ref "U1") (pin "12") (pinfunction "GPIO.2_12") (pintype "passive"))
      (node (ref "U3") (pin "38") (pinfunction "~{U1RTS/BCLK1/CN21/RD15}_38") (pintype "bidirectional"))
    )
    (net (code "83") (name "USB_RXD") (class "Default")
      (node (ref "U1") (pin "20") (pinfunction "RXD_20") (pintype "input"))
      (node (ref "U3") (pin "40") (pinfunction "PMA8/U2TX/CN18/RF5_40") (pintype "bidirectional"))
    )
    (net (code "84") (name "USB_TXD") (class "Default")
      (node (ref "U1") (pin "21") (pinfunction "TXD_21") (pintype "output"))
      (node (ref "U3") (pin "39") (pinfunction "PMA9/U2RX/CN17/RF4_39") (pintype "bidirectional"))
    )
    (net (code "85") (name "WIFI_INT_") (class "Default")
      (node (ref "J6") (pin "7") (pinfunction "7_7") (pintype "passive"))
      (node (ref "U3") (pin "13") (pinfunction "TMS/INT1/RE8_13") (pintype "bidirectional"))
    )
    (net (code "86") (name "WIND_COUNT_IN") (class "Default")
      (node (ref "J1") (pin "P$8") (pinfunction "8_P$8") (pintype "bidirectional"))
      (node (ref "R1") (pin "1") (pinfunction "1_1") (pintype "passive"))
    )
    (net (code "87") (name "WIN_DIR_IN") (class "Default")
      (node (ref "J1") (pin "P$4") (pinfunction "4_P$4") (pintype "bidirectional"))
      (node (ref "R5") (pin "1") (pinfunction "1_1") (pintype "passive"))
    )
    (net (code "88") (name "unconnected-(+5V-Pad2)") (class "Default")
      (node (ref "+5V") (pin "2") (pinfunction "2_2") (pintype "passive"))
    )
    (net (code "89") (name "unconnected-(FAN-Pad2)") (class "Default")
      (node (ref "FAN") (pin "2") (pinfunction "2_2") (pintype "passive"))
    )
    (net (code "90") (name "unconnected-(J5-6-PadP$6)") (class "Default")
      (node (ref "J5") (pin "P$6") (pinfunction "6_P$6") (pintype "bidirectional"))
    )
    (net (code "91") (name "unconnected-(J6-Pad1)") (class "Default")
      (node (ref "J6") (pin "1") (pinfunction "1_1") (pintype "passive"))
    )
    (net (code "92") (name "unconnected-(U1-*RST-Pad9)") (class "Default")
      (node (ref "U1") (pin "9") (pinfunction "*RST_9") (pintype "passive"))
    )
    (net (code "93") (name "unconnected-(U1-*SUSPEND-Pad15)") (class "Default")
      (node (ref "U1") (pin "15") (pinfunction "*SUSPEND_15") (pintype "output"))
    )
    (net (code "94") (name "unconnected-(U1-CTS-Pad18)") (class "Default")
      (node (ref "U1") (pin "18") (pinfunction "CTS_18") (pintype "input"))
    )
    (net (code "95") (name "unconnected-(U1-DCD-Pad24)") (class "Default")
      (node (ref "U1") (pin "24") (pinfunction "DCD_24") (pintype "input"))
    )
    (net (code "96") (name "unconnected-(U1-DSR-Pad22)") (class "Default")
      (node (ref "U1") (pin "22") (pinfunction "DSR_22") (pintype "input"))
    )
    (net (code "97") (name "unconnected-(U1-DTR-Pad23)") (class "Default")
      (node (ref "U1") (pin "23") (pinfunction "DTR_23") (pintype "output"))
    )
    (net (code "98") (name "unconnected-(U1-GPIO.3-Pad11)") (class "Default")
      (node (ref "U1") (pin "11") (pinfunction "GPIO.3_11") (pintype "passive"))
    )
    (net (code "99") (name "unconnected-(U1-NC-Pad10)") (class "Default")
      (node (ref "U1") (pin "10") (pinfunction "NC_10") (pintype "no_connect"))
    )
    (net (code "100") (name "unconnected-(U1-RI-Pad1)") (class "Default")
      (node (ref "U1") (pin "1") (pinfunction "RI_1") (pintype "input"))
    )
    (net (code "101") (name "unconnected-(U1-RTS-Pad19)") (class "Default")
      (node (ref "U1") (pin "19") (pinfunction "RTS_19") (pintype "output"))
    )
    (net (code "102") (name "unconnected-(U1-SUSPEND-Pad17)") (class "Default")
      (node (ref "U1") (pin "17") (pinfunction "SUSPEND_17") (pintype "output"))
    )
    (net (code "103") (name "unconnected-(U1-VPP-Pad16)") (class "Default")
      (node (ref "U1") (pin "16") (pinfunction "VPP_16") (pintype "passive"))
    )
    (net (code "104") (name "unconnected-(USB-Pad4_ID)") (class "Default")
      (node (ref "USB") (pin "4_ID") (pinfunction "4_ID_4_ID") (pintype "passive"))
    )
  )
)
